# board.net
KiCad netlist of a schematic drawn in EAGLE
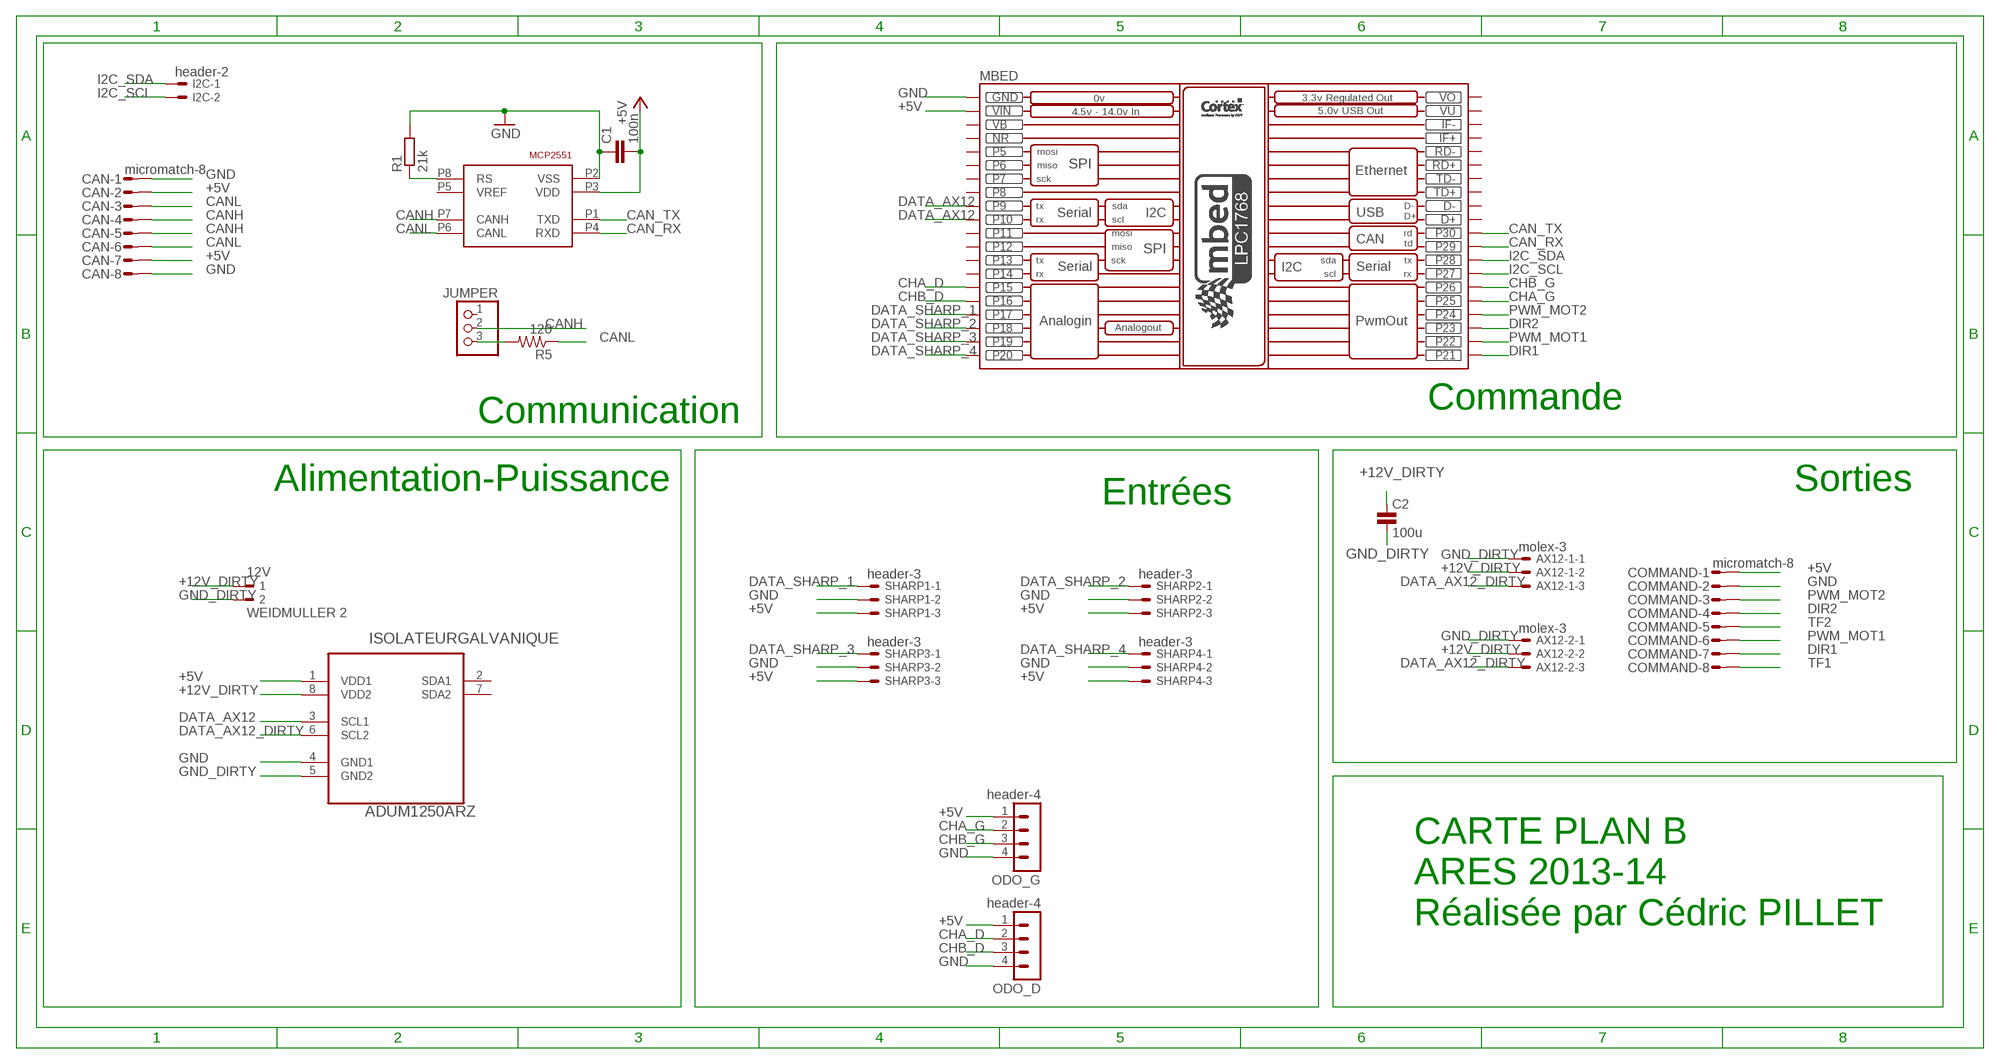
[diagram p0: schematic, sheet 1]

(export (version "E")
  (design (tool "Eeschema 10.0.6"))
  (components
    (comp (ref "12V")
      (value "WEIDMULLER 2")
      (footprint "eagle-import:90G-2")
      (libsource (lib "eagle-import") (part "90G-2"))
    )
    (comp (ref "AX12-1")
      (value "molex-3")
      (footprint "eagle-import:22-23-2031")
      (fields (field (name "MF") "MOLEX") (field (name "MPN") "22-23-2031"))
      (libsource (lib "eagle-import") (part "22-23-2031"))
    )
    (comp (ref "AX12-2")
      (value "molex-3")
      (footprint "eagle-import:22-23-2031")
      (fields (field (name "MF") "MOLEX") (field (name "MPN") "22-23-2031"))
      (libsource (lib "eagle-import") (part "22-23-2031"))
    )
    (comp (ref "C1")
      (value "100n")
      (footprint "eagle-import:C0805")
      (libsource (lib "eagle-import") (part "C-EUC0805"))
    )
    (comp (ref "C2")
      (value "100u")
      (footprint "eagle-import:0805")
      (libsource (lib "eagle-import") (part "C0805"))
    )
    (comp (ref "CAN")
      (value "micromatch-8")
      (footprint "eagle-import:MICROMATCH-8")
      (fields (field (name "MF") "FARNELL") (field (name "MPN") "7-215464-8"))
      (libsource (lib "eagle-import") (part "MICROMATCH-8"))
    )
    (comp (ref "COMMAND")
      (value "micromatch-8")
      (footprint "eagle-import:MICROMATCH-8")
      (fields (field (name "MF") "FARNELL") (field (name "MPN") "7-215464-8"))
      (libsource (lib "eagle-import") (part "MICROMATCH-8"))
    )
    (comp (ref "I2C")
      (value "header-2")
      (footprint "eagle-import:22-23-2021")
      (fields (field (name "MF") "MOLEX") (field (name "MPN") "22-23-2021"))
      (libsource (lib "eagle-import") (part "22-23-2021"))
    )
    (comp (ref "ISOLATEURGALVANIQUE")
      (value "ADUM1250ARZ")
      (footprint "eagle-import:SOIC127P600X175-8N")
      (libsource (lib "eagle-import") (part "ADUM1250ARZ"))
    )
    (comp (ref "JUMPER")
      (value "PINHD-1X3")
      (footprint "eagle-import:1X03")
      (libsource (lib "eagle-import") (part "PINHD-1X3"))
    )
    (comp (ref "MBED")
      (value "MBED_NXP_LPC1768")
      (footprint "eagle-import:MBED-KIT")
      (libsource (lib "eagle-import") (part "MBED_NXP_LPC1768"))
    )
    (comp (ref "ODO_D")
      (value "header-4")
      (footprint "eagle-import:MA04-1")
      (libsource (lib "eagle-import") (part "MA04-1"))
    )
    (comp (ref "ODO_G")
      (value "header-4")
      (footprint "eagle-import:MA04-1")
      (libsource (lib "eagle-import") (part "MA04-1"))
    )
    (comp (ref "R1")
      (value "21k")
      (footprint "eagle-import:R0805")
      (libsource (lib "eagle-import") (part "R-EU_R0805"))
    )
    (comp (ref "R5")
      (value "120")
      (footprint "eagle-import:M0805")
      (libsource (lib "eagle-import") (part "R-US_M0805"))
    )
    (comp (ref "SHARP1")
      (value "header-3")
      (footprint "eagle-import:22-23-2031")
      (fields (field (name "MF") "MOLEX") (field (name "MPN") "22-23-2031"))
      (libsource (lib "eagle-import") (part "22-23-2031"))
    )
    (comp (ref "SHARP2")
      (value "header-3")
      (footprint "eagle-import:22-23-2031")
      (fields (field (name "MF") "MOLEX") (field (name "MPN") "22-23-2031"))
      (libsource (lib "eagle-import") (part "22-23-2031"))
    )
    (comp (ref "SHARP3")
      (value "header-3")
      (footprint "eagle-import:22-23-2031")
      (fields (field (name "MF") "MOLEX") (field (name "MPN") "22-23-2031"))
      (libsource (lib "eagle-import") (part "22-23-2031"))
    )
    (comp (ref "SHARP4")
      (value "header-3")
      (footprint "eagle-import:22-23-2031")
      (fields (field (name "MF") "MOLEX") (field (name "MPN") "22-23-2031"))
      (libsource (lib "eagle-import") (part "22-23-2031"))
    )
    (comp (ref "TRANSCEIVER")
      (value "MCP2551")
      (footprint "eagle-import:SOIC_8")
      (libsource (lib "eagle-import") (part "MCP2551"))
    )
  )
  (nets
    (net (code "1") (name "+5V") (class "Default")
      (node (ref "C1") (pin "2") (pinfunction "2_2") (pintype "passive"))
      (node (ref "CAN") (pin "2") (pinfunction "S_2") (pintype "passive"))
      (node (ref "CAN") (pin "7") (pinfunction "S_7") (pintype "passive"))
      (node (ref "COMMAND") (pin "1") (pinfunction "S_1") (pintype "passive"))
      (node (ref "ISOLATEURGALVANIQUE") (pin "1") (pinfunction "VDD1_1") (pintype "power_in"))
      (node (ref "MBED") (pin "VIN") (pinfunction "VIN_VIN") (pintype "power_in"))
      (node (ref "ODO_D") (pin "1") (pinfunction "1_1") (pintype "passive"))
      (node (ref "ODO_G") (pin "1") (pinfunction "1_1") (pintype "passive"))
      (node (ref "SHARP1") (pin "3") (pinfunction "S_3") (pintype "passive"))
      (node (ref "SHARP2") (pin "3") (pinfunction "S_3") (pintype "passive"))
      (node (ref "SHARP3") (pin "3") (pinfunction "S_3") (pintype "passive"))
      (node (ref "SHARP4") (pin "3") (pinfunction "S_3") (pintype "passive"))
      (node (ref "TRANSCEIVER") (pin "P3") (pinfunction "VDD_P3") (pintype "bidirectional"))
    )
    (net (code "2") (name "/+12V_DIRTY") (class "Default")
      (node (ref "12V") (pin "1") (pinfunction "1_1") (pintype "passive"))
      (node (ref "AX12-1") (pin "2") (pinfunction "S_2") (pintype "passive"))
      (node (ref "AX12-2") (pin "2") (pinfunction "S_2") (pintype "passive"))
      (node (ref "C2") (pin "1") (pinfunction "P$1_1") (pintype "passive"))
      (node (ref "ISOLATEURGALVANIQUE") (pin "8") (pinfunction "VDD2_8") (pintype "power_in"))
    )
    (net (code "3") (name "/CANH") (class "Default")
      (node (ref "CAN") (pin "4") (pinfunction "S_4") (pintype "passive"))
      (node (ref "CAN") (pin "5") (pinfunction "S_5") (pintype "passive"))
      (node (ref "JUMPER") (pin "2") (pinfunction "2_2") (pintype "passive"))
      (node (ref "TRANSCEIVER") (pin "P7") (pinfunction "CANH_P7") (pintype "bidirectional"))
    )
    (net (code "4") (name "/CANL") (class "Default")
      (node (ref "CAN") (pin "3") (pinfunction "S_3") (pintype "passive"))
      (node (ref "CAN") (pin "6") (pinfunction "S_6") (pintype "passive"))
      (node (ref "R5") (pin "1") (pinfunction "1_1") (pintype "passive"))
      (node (ref "TRANSCEIVER") (pin "P6") (pinfunction "CANL_P6") (pintype "bidirectional"))
    )
    (net (code "5") (name "/CAN_RX") (class "Default")
      (node (ref "MBED") (pin "P$29") (pinfunction "P29_P$29") (pintype "bidirectional"))
      (node (ref "TRANSCEIVER") (pin "P4") (pinfunction "RXD_P4") (pintype "bidirectional"))
    )
    (net (code "6") (name "/CAN_TX") (class "Default")
      (node (ref "MBED") (pin "P$30") (pinfunction "P30_P$30") (pintype "bidirectional"))
      (node (ref "TRANSCEIVER") (pin "P1") (pinfunction "TXD_P1") (pintype "bidirectional"))
    )
    (net (code "7") (name "/CHA_D") (class "Default")
      (node (ref "MBED") (pin "P$15") (pinfunction "P15_P$15") (pintype "bidirectional"))
      (node (ref "ODO_D") (pin "2") (pinfunction "2_2") (pintype "passive"))
    )
    (net (code "8") (name "/CHA_G") (class "Default")
      (node (ref "MBED") (pin "P$25") (pinfunction "P25_P$25") (pintype "bidirectional"))
      (node (ref "ODO_G") (pin "2") (pinfunction "2_2") (pintype "passive"))
    )
    (net (code "9") (name "/CHB_D") (class "Default")
      (node (ref "MBED") (pin "P$16") (pinfunction "P16_P$16") (pintype "bidirectional"))
      (node (ref "ODO_D") (pin "3") (pinfunction "3_3") (pintype "passive"))
    )
    (net (code "10") (name "/CHB_G") (class "Default")
      (node (ref "MBED") (pin "P$26") (pinfunction "P26_P$26") (pintype "bidirectional"))
      (node (ref "ODO_G") (pin "3") (pinfunction "3_3") (pintype "passive"))
    )
    (net (code "11") (name "/DATA_AX12") (class "Default")
      (node (ref "ISOLATEURGALVANIQUE") (pin "3") (pinfunction "SCL1_3") (pintype "input"))
      (node (ref "MBED") (pin "P$10") (pinfunction "P10_P$10") (pintype "bidirectional"))
      (node (ref "MBED") (pin "P$9") (pinfunction "P9_P$9") (pintype "bidirectional"))
    )
    (net (code "12") (name "/DATA_AX12_DIRTY") (class "Default")
      (node (ref "AX12-1") (pin "3") (pinfunction "S_3") (pintype "passive"))
      (node (ref "AX12-2") (pin "3") (pinfunction "S_3") (pintype "passive"))
      (node (ref "ISOLATEURGALVANIQUE") (pin "6") (pinfunction "SCL2_6") (pintype "input"))
    )
    (net (code "13") (name "/DATA_SHARP_1") (class "Default")
      (node (ref "MBED") (pin "P$17") (pinfunction "P17_P$17") (pintype "bidirectional"))
      (node (ref "SHARP1") (pin "1") (pinfunction "S_1") (pintype "passive"))
    )
    (net (code "14") (name "/DATA_SHARP_2") (class "Default")
      (node (ref "MBED") (pin "P$18") (pinfunction "P18_P$18") (pintype "bidirectional"))
      (node (ref "SHARP2") (pin "1") (pinfunction "S_1") (pintype "passive"))
    )
    (net (code "15") (name "/DATA_SHARP_3") (class "Default")
      (node (ref "MBED") (pin "P$19") (pinfunction "P19_P$19") (pintype "bidirectional"))
      (node (ref "SHARP3") (pin "1") (pinfunction "S_1") (pintype "passive"))
    )
    (net (code "16") (name "/DATA_SHARP_4") (class "Default")
      (node (ref "MBED") (pin "P$20") (pinfunction "P20_P$20") (pintype "bidirectional"))
      (node (ref "SHARP4") (pin "1") (pinfunction "S_1") (pintype "passive"))
    )
    (net (code "17") (name "/DIR1") (class "Default")
      (node (ref "COMMAND") (pin "7") (pinfunction "S_7") (pintype "passive"))
      (node (ref "MBED") (pin "P$21") (pinfunction "P21_P$21") (pintype "bidirectional"))
    )
    (net (code "18") (name "/DIR2") (class "Default")
      (node (ref "COMMAND") (pin "4") (pinfunction "S_4") (pintype "passive"))
      (node (ref "MBED") (pin "P$23") (pinfunction "P23_P$23") (pintype "bidirectional"))
    )
    (net (code "19") (name "/GND_DIRTY") (class "Default")
      (node (ref "12V") (pin "2") (pinfunction "2_2") (pintype "passive"))
      (node (ref "AX12-1") (pin "1") (pinfunction "S_1") (pintype "passive"))
      (node (ref "AX12-2") (pin "1") (pinfunction "S_1") (pintype "passive"))
      (node (ref "C2") (pin "2") (pinfunction "P$2_2") (pintype "passive"))
      (node (ref "ISOLATEURGALVANIQUE") (pin "5") (pinfunction "GND2_5") (pintype "passive"))
    )
    (net (code "20") (name "/I2C_SCL") (class "Default")
      (node (ref "I2C") (pin "2") (pinfunction "S_2") (pintype "passive"))
      (node (ref "MBED") (pin "P$27") (pinfunction "P27_P$27") (pintype "bidirectional"))
    )
    (net (code "21") (name "/I2C_SDA") (class "Default")
      (node (ref "I2C") (pin "1") (pinfunction "S_1") (pintype "passive"))
      (node (ref "MBED") (pin "P$28") (pinfunction "P28_P$28") (pintype "bidirectional"))
    )
    (net (code "22") (name "/NR") (class "Default")
      (node (ref "MBED") (pin "NR") (pinfunction "NR_NR") (pintype "power_in"))
    )
    (net (code "23") (name "/PWM_MOT1") (class "Default")
      (node (ref "COMMAND") (pin "6") (pinfunction "S_6") (pintype "passive"))
      (node (ref "MBED") (pin "P$22") (pinfunction "P22_P$22") (pintype "bidirectional"))
    )
    (net (code "24") (name "/PWM_MOT2") (class "Default")
      (node (ref "COMMAND") (pin "3") (pinfunction "S_3") (pintype "passive"))
      (node (ref "MBED") (pin "P$24") (pinfunction "P24_P$24") (pintype "bidirectional"))
    )
    (net (code "25") (name "/TF1") (class "Default")
      (node (ref "COMMAND") (pin "8") (pinfunction "S_8") (pintype "passive"))
    )
    (net (code "26") (name "/TF2") (class "Default")
      (node (ref "COMMAND") (pin "5") (pinfunction "S_5") (pintype "passive"))
    )
    (net (code "27") (name "/VB") (class "Default")
      (node (ref "MBED") (pin "VB") (pinfunction "VB_VB") (pintype "power_in"))
    )
    (net (code "28") (name "/VO") (class "Default")
      (node (ref "MBED") (pin "VOUT") (pinfunction "VO_VOUT") (pintype "power_in"))
    )
    (net (code "29") (name "/VU") (class "Default")
      (node (ref "MBED") (pin "VU") (pinfunction "VU_VU") (pintype "power_in"))
    )
    (net (code "30") (name "GND") (class "Default")
      (node (ref "C1") (pin "1") (pinfunction "1_1") (pintype "passive"))
      (node (ref "CAN") (pin "1") (pinfunction "S_1") (pintype "passive"))
      (node (ref "CAN") (pin "8") (pinfunction "S_8") (pintype "passive"))
      (node (ref "COMMAND") (pin "2") (pinfunction "S_2") (pintype "passive"))
      (node (ref "ISOLATEURGALVANIQUE") (pin "4") (pinfunction "GND1_4") (pintype "passive"))
      (node (ref "MBED") (pin "GND") (pinfunction "GND_GND") (pintype "power_in"))
      (node (ref "ODO_D") (pin "4") (pinfunction "4_4") (pintype "passive"))
      (node (ref "ODO_G") (pin "4") (pinfunction "4_4") (pintype "passive"))
      (node (ref "R1") (pin "2") (pinfunction "2_2") (pintype "passive"))
      (node (ref "SHARP1") (pin "2") (pinfunction "S_2") (pintype "passive"))
      (node (ref "SHARP2") (pin "2") (pinfunction "S_2") (pintype "passive"))
      (node (ref "SHARP3") (pin "2") (pinfunction "S_2") (pintype "passive"))
      (node (ref "SHARP4") (pin "2") (pinfunction "S_2") (pintype "passive"))
      (node (ref "TRANSCEIVER") (pin "P2") (pinfunction "VSS_P2") (pintype "bidirectional"))
    )
    (net (code "31") (name "Net-(JUMPER-Pad3)") (class "Default")
      (node (ref "JUMPER") (pin "3") (pinfunction "3_3") (pintype "passive"))
      (node (ref "R5") (pin "2") (pinfunction "2_2") (pintype "passive"))
    )
    (net (code "32") (name "Net-(TRANSCEIVER-RS)") (class "Default")
      (node (ref "R1") (pin "1") (pinfunction "1_1") (pintype "passive"))
      (node (ref "TRANSCEIVER") (pin "P8") (pinfunction "RS_P8") (pintype "bidirectional"))
    )
    (net (code "33") (name "unconnected-(ISOLATEURGALVANIQUE-SDA1-Pad2)") (class "Default")
      (node (ref "ISOLATEURGALVANIQUE") (pin "2") (pinfunction "SDA1_2") (pintype "bidirectional"))
    )
    (net (code "34") (name "unconnected-(ISOLATEURGALVANIQUE-SDA2-Pad7)") (class "Default")
      (node (ref "ISOLATEURGALVANIQUE") (pin "7") (pinfunction "SDA2_7") (pintype "bidirectional"))
    )
    (net (code "35") (name "unconnected-(JUMPER-Pad1)") (class "Default")
      (node (ref "JUMPER") (pin "1") (pinfunction "1_1") (pintype "passive"))
    )
    (net (code "36") (name "unconnected-(MBED-P5-PadP$5)") (class "Default")
      (node (ref "MBED") (pin "P$5") (pinfunction "P5_P$5") (pintype "bidirectional"))
    )
    (net (code "37") (name "unconnected-(MBED-P6-PadP$6)") (class "Default")
      (node (ref "MBED") (pin "P$6") (pinfunction "P6_P$6") (pintype "bidirectional"))
    )
    (net (code "38") (name "unconnected-(MBED-P7-PadP$7)") (class "Default")
      (node (ref "MBED") (pin "P$7") (pinfunction "P7_P$7") (pintype "bidirectional"))
    )
    (net (code "39") (name "unconnected-(MBED-P8-PadP$8)") (class "Default")
      (node (ref "MBED") (pin "P$8") (pinfunction "P8_P$8") (pintype "bidirectional"))
    )
    (net (code "40") (name "unconnected-(MBED-P11-PadP$11)") (class "Default")
      (node (ref "MBED") (pin "P$11") (pinfunction "P11_P$11") (pintype "bidirectional"))
    )
    (net (code "41") (name "unconnected-(MBED-P12-PadP$12)") (class "Default")
      (node (ref "MBED") (pin "P$12") (pinfunction "P12_P$12") (pintype "bidirectional"))
    )
    (net (code "42") (name "unconnected-(MBED-P13-PadP$13)") (class "Default")
      (node (ref "MBED") (pin "P$13") (pinfunction "P13_P$13") (pintype "bidirectional"))
    )
    (net (code "43") (name "unconnected-(MBED-P14-PadP$14)") (class "Default")
      (node (ref "MBED") (pin "P$14") (pinfunction "P14_P$14") (pintype "bidirectional"))
    )
    (net (code "44") (name "unconnected-(MBED-PadD+)") (class "Default")
      (node (ref "MBED") (pin "D+") (pinfunction "D+_D+") (pintype "bidirectional"))
    )
    (net (code "45") (name "unconnected-(MBED-PadD-)") (class "Default")
      (node (ref "MBED") (pin "D-") (pinfunction "D-_D-") (pintype "bidirectional"))
    )
    (net (code "46") (name "unconnected-(MBED-PadIF+)") (class "Default")
      (node (ref "MBED") (pin "IF+") (pinfunction "IF+_IF+") (pintype "bidirectional"))
    )
    (net (code "47") (name "unconnected-(MBED-PadIF-)") (class "Default")
      (node (ref "MBED") (pin "IF-") (pinfunction "IF-_IF-") (pintype "bidirectional"))
    )
    (net (code "48") (name "unconnected-(MBED-PadRD+)") (class "Default")
      (node (ref "MBED") (pin "RD+") (pinfunction "RD+_RD+") (pintype "bidirectional"))
    )
    (net (code "49") (name "unconnected-(MBED-PadRD-)") (class "Default")
      (node (ref "MBED") (pin "RD-") (pinfunction "RD-_RD-") (pintype "bidirectional"))
    )
    (net (code "50") (name "unconnected-(MBED-PadTD+)") (class "Default")
      (node (ref "MBED") (pin "TD+") (pinfunction "TD+_TD+") (pintype "bidirectional"))
    )
    (net (code "51") (name "unconnected-(MBED-PadTD-)") (class "Default")
      (node (ref "MBED") (pin "TD-") (pinfunction "TD-_TD-") (pintype "bidirectional"))
    )
    (net (code "52") (name "unconnected-(TRANSCEIVER-VREF-PadP5)") (class "Default")
      (node (ref "TRANSCEIVER") (pin "P5") (pinfunction "VREF_P5") (pintype "bidirectional"))
    )
  )
)
